# Connectors.net
KiCad netlist of a schematic drawn in Altium Designer
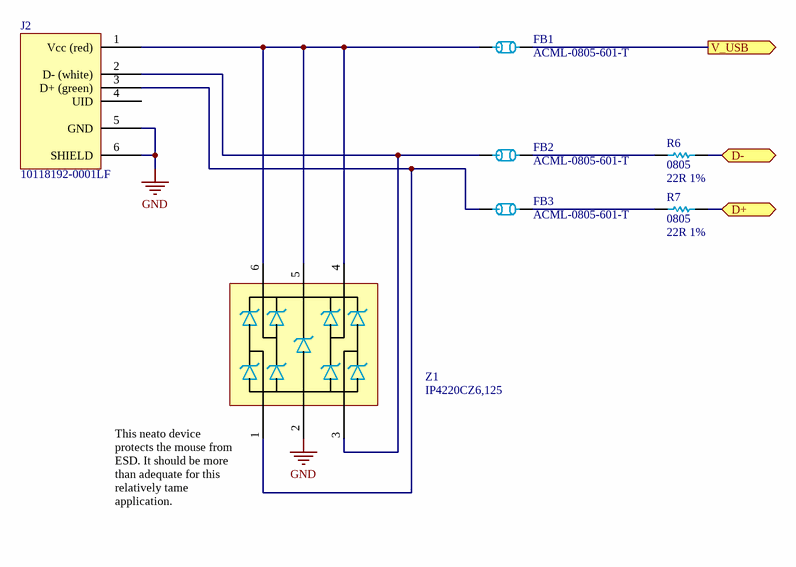
[diagram p0: Connectors.SchDoc]

(export (version "E")
  (design (tool "Eeschema 10.0.6"))
  (components
    (comp (ref "FB1")
      (value "ACML-0805-601-T")
      (footprint "0805")
      (description "FERRITE BEAD 600 OHM 0805 1LN")
      (libsource (lib "Chip_Passives") (part "ACML-0805-601-T"))
    )
    (comp (ref "FB2")
      (value "ACML-0805-601-T")
      (footprint "0805")
      (description "FERRITE BEAD 600 OHM 0805 1LN")
      (libsource (lib "Chip_Passives") (part "ACML-0805-601-T"))
    )
    (comp (ref "FB3")
      (value "ACML-0805-601-T")
      (footprint "0805")
      (description "FERRITE BEAD 600 OHM 0805 1LN")
      (libsource (lib "Chip_Passives") (part "ACML-0805-601-T"))
    )
    (comp (ref "J2")
      (value "10118192-0001LF")
      (footprint "10118192-0001LF")
      (description "CONN RCPT USB2.0 MICRO B SMD R/A")
      (libsource (lib "Connectors") (part "10118192-0001LF"))
    )
    (comp (ref "R6")
      (value "0805")
      (footprint "0805")
      (description "Chip resistor")
      (fields (field (name "ALTIUM_VALUE") "22R 1%"))
      (libsource (lib "Chip_Passives") (part "Res 22R 1% 0805"))
    )
    (comp (ref "R7")
      (value "0805")
      (footprint "0805")
      (description "Chip resistor")
      (fields (field (name "ALTIUM_VALUE") "22R 1%"))
      (libsource (lib "Chip_Passives") (part "Res 22R 1% 0805"))
    )
    (comp (ref "Z1")
      (value "IP4220CZ6,125")
      (footprint "PESD3V3S4UD - SOT95P275X110-6N")
      (description "TVS DIODE 5.5V 6TSOP (Low capacitance, USB)")
      (libsource (lib "Diodes") (part "IP4220CZ6,125"))
    )
  )
  (nets
    (net (code "1") (name "/D+") (class "Default")
      (node (ref "R7") (pin "2") (pinfunction "2_2") (pintype "passive"))
    )
    (net (code "2") (name "/D-") (class "Default")
      (node (ref "R6") (pin "2") (pinfunction "2_2") (pintype "passive"))
    )
    (net (code "3") (name "/V_USB") (class "Default")
      (node (ref "FB1") (pin "2") (pinfunction "2_2") (pintype "passive"))
    )
    (net (code "4") (name "GND") (class "Default")
      (node (ref "J2") (pin "5") (pinfunction "GND_5") (pintype "passive"))
      (node (ref "J2") (pin "6") (pinfunction "SHIELD_6") (pintype "passive"))
      (node (ref "Z1") (pin "2") (pinfunction "2_2") (pintype "passive"))
    )
    (net (code "5") (name "Net-(FB2-Pad2)") (class "Default")
      (node (ref "FB2") (pin "2") (pinfunction "2_2") (pintype "passive"))
      (node (ref "R6") (pin "1") (pinfunction "1_1") (pintype "passive"))
    )
    (net (code "6") (name "Net-(FB3-Pad2)") (class "Default")
      (node (ref "FB3") (pin "2") (pinfunction "2_2") (pintype "passive"))
      (node (ref "R7") (pin "1") (pinfunction "1_1") (pintype "passive"))
    )
    (net (code "7") (name "Net-(J2-D+_(green))") (class "Default")
      (node (ref "FB3") (pin "1") (pinfunction "1_1") (pintype "passive"))
      (node (ref "J2") (pin "3") (pinfunction "D+_(green)_3") (pintype "passive"))
      (node (ref "Z1") (pin "1") (pinfunction "1_1") (pintype "passive"))
    )
    (net (code "8") (name "Net-(J2-D-_(white))") (class "Default")
      (node (ref "FB2") (pin "1") (pinfunction "1_1") (pintype "passive"))
      (node (ref "J2") (pin "2") (pinfunction "D-_(white)_2") (pintype "passive"))
      (node (ref "Z1") (pin "3") (pinfunction "3_3") (pintype "passive"))
    )
    (net (code "9") (name "Net-(J2-Vcc_(red))") (class "Default")
      (node (ref "FB1") (pin "1") (pinfunction "1_1") (pintype "passive"))
      (node (ref "J2") (pin "1") (pinfunction "Vcc_(red)_1") (pintype "passive"))
      (node (ref "Z1") (pin "4") (pinfunction "4_4") (pintype "passive"))
      (node (ref "Z1") (pin "5") (pinfunction "5_5") (pintype "passive"))
      (node (ref "Z1") (pin "6") (pinfunction "6_6") (pintype "passive"))
    )
    (net (code "10") (name "unconnected-(J2-UID-Pad4)") (class "Default")
      (node (ref "J2") (pin "4") (pinfunction "UID_4") (pintype "passive"))
    )
  )
)
